# amp_schematic.net
KiCad netlist of a schematic drawn in EAGLE
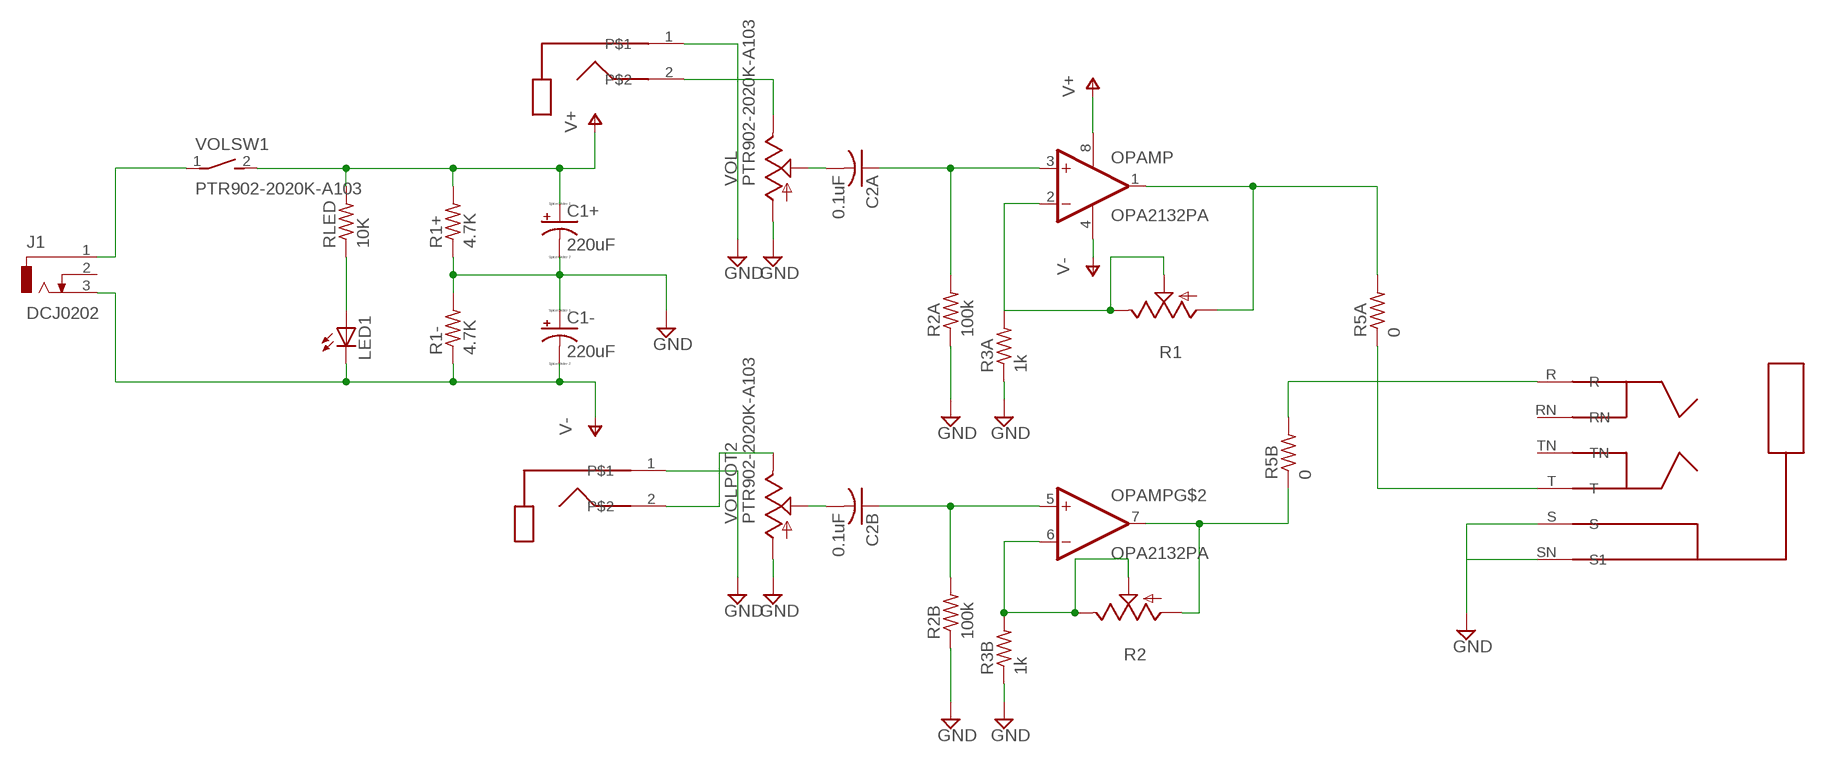
[diagram p0: schematic, sheet 1]

(export (version "E")
  (design (tool "Eeschema 10.0.6"))
  (components
    (comp (ref "C1+")
      (value "220uF")
      (footprint "eagle-import:E3,5-8")
      (libsource (lib "eagle-import") (part "CPOL-USE3.5-8"))
    )
    (comp (ref "C1-")
      (value "220uF")
      (footprint "eagle-import:E3,5-8")
      (libsource (lib "eagle-import") (part "CPOL-USE3.5-8"))
    )
    (comp (ref "C2A")
      (value "0.1uF")
      (footprint "eagle-import:C050-025X075")
      (libsource (lib "eagle-import") (part "C-US050-025X075"))
    )
    (comp (ref "C2B")
      (value "0.1uF")
      (footprint "eagle-import:C050-025X075")
      (libsource (lib "eagle-import") (part "C-US050-025X075"))
    )
    (comp (ref "J1")
      (value "DCJ0202")
      (footprint "eagle-import:DCJ0202")
      (libsource (lib "eagle-import") (part "DCJ0202"))
    )
    (comp (ref "LED1")
      (value "LED5MM")
      (footprint "eagle-import:LED5MM")
      (libsource (lib "eagle-import") (part "LED5MM"))
    )
    (comp (ref "LEFT")
      (value "RCAJACK")
      (footprint "eagle-import:RCAJACK")
      (libsource (lib "eagle-import") (part "RCAJACK"))
    )
    (comp (ref "OPAMP")
      (value "OPA2132PA")
      (footprint "eagle-import:DIP254P762X508-8")
      (fields (field (name "DIGI-KEY_PART_NUMBER") "OPA2132PA-ND") (field (name "MF") "Texas Instruments"))
      (libsource (lib "eagle-import") (part "OPA2132PA"))
    )
    (comp (ref "OUTPUT")
      (value "STEROJACK")
      (footprint "eagle-import:STEREOJACK")
      (libsource (lib "eagle-import") (part "STEROJACK"))
    )
    (comp (ref "R1")
      (value "TRIM_US-B25U")
      (footprint "eagle-import:B25U")
      (libsource (lib "eagle-import") (part "TRIM_US-B25U"))
    )
    (comp (ref "R1+")
      (value "4.7K")
      (footprint "eagle-import:0204V")
      (libsource (lib "eagle-import") (part "R-US_0204/2V"))
    )
    (comp (ref "R1-")
      (value "4.7K")
      (footprint "eagle-import:0204V")
      (libsource (lib "eagle-import") (part "R-US_0204/2V"))
    )
    (comp (ref "R2")
      (value "TRIM_US-B25U")
      (footprint "eagle-import:B25U")
      (libsource (lib "eagle-import") (part "TRIM_US-B25U"))
    )
    (comp (ref "R2A")
      (value "100k")
      (footprint "eagle-import:0204V")
      (libsource (lib "eagle-import") (part "R-US_0204/2V"))
    )
    (comp (ref "R2B")
      (value "100k")
      (footprint "eagle-import:0204V")
      (libsource (lib "eagle-import") (part "R-US_0204/2V"))
    )
    (comp (ref "R3A")
      (value "1k")
      (footprint "eagle-import:0204V")
      (libsource (lib "eagle-import") (part "R-US_0204/2V"))
    )
    (comp (ref "R3B")
      (value "1k")
      (footprint "eagle-import:0204V")
      (libsource (lib "eagle-import") (part "R-US_0204/2V"))
    )
    (comp (ref "R5A")
      (value "0")
      (footprint "eagle-import:0204V")
      (libsource (lib "eagle-import") (part "R-US_0204/2V"))
    )
    (comp (ref "R5B")
      (value "0")
      (footprint "eagle-import:0204V")
      (libsource (lib "eagle-import") (part "R-US_0204/2V"))
    )
    (comp (ref "RIGHT")
      (value "RCAJACK")
      (footprint "eagle-import:RCAJACK")
      (libsource (lib "eagle-import") (part "RCAJACK"))
    )
    (comp (ref "RLED")
      (value "10K")
      (footprint "eagle-import:0204V")
      (libsource (lib "eagle-import") (part "R-US_0204/2V"))
    )
    (comp (ref "VOL")
      (value "PTR902-2020K-A103")
      (footprint "eagle-import:PTR902")
      (libsource (lib "eagle-import") (part "PTR902-2020K-A103"))
    )
  )
  (nets
    (net (code "1") (name "GND") (class "Default")
      (node (ref "C1+") (pin "-") (pinfunction "-_-") (pintype "passive"))
      (node (ref "C1-") (pin "+") (pinfunction "+_+") (pintype "passive"))
      (node (ref "LEFT") (pin "1") (pinfunction "P$1_1") (pintype "bidirectional"))
      (node (ref "OUTPUT") (pin "S") (pinfunction "S_S") (pintype "bidirectional"))
      (node (ref "OUTPUT") (pin "SN") (pinfunction "S1_SN") (pintype "bidirectional"))
      (node (ref "R1+") (pin "1") (pinfunction "1_1") (pintype "passive"))
      (node (ref "R1-") (pin "2") (pinfunction "2_2") (pintype "passive"))
      (node (ref "R2A") (pin "1") (pinfunction "1_1") (pintype "passive"))
      (node (ref "R2B") (pin "1") (pinfunction "1_1") (pintype "passive"))
      (node (ref "R3A") (pin "1") (pinfunction "1_1") (pintype "passive"))
      (node (ref "R3B") (pin "1") (pinfunction "1_1") (pintype "passive"))
      (node (ref "RIGHT") (pin "1") (pinfunction "P$1_1") (pintype "bidirectional"))
      (node (ref "VOL") (pin "1A") (pinfunction "A_1A") (pintype "passive"))
      (node (ref "VOL") (pin "1B") (pinfunction "A_1B") (pintype "passive"))
    )
    (net (code "2") (name "Net-(LED1-PadA)") (class "Default")
      (node (ref "LED1") (pin "A") (pinfunction "A_A") (pintype "passive"))
      (node (ref "RLED") (pin "1") (pinfunction "1_1") (pintype "passive"))
    )
    (net (code "3") (name "Net-(LEFT-P$2)") (class "Default")
      (node (ref "LEFT") (pin "2") (pinfunction "P$2_2") (pintype "bidirectional"))
      (node (ref "VOL") (pin "3A") (pinfunction "E_3A") (pintype "passive"))
    )
    (net (code "4") (name "Net-(OPAMPA-+INA)") (class "Default")
      (node (ref "C2A") (pin "1") (pinfunction "1_1") (pintype "passive"))
      (node (ref "OPAMP") (pin "3") (pinfunction "+INA_3") (pintype "input"))
      (node (ref "R2A") (pin "2") (pinfunction "2_2") (pintype "passive"))
    )
    (net (code "5") (name "Net-(OPAMPA--INA)") (class "Default")
      (node (ref "OPAMP") (pin "2") (pinfunction "-INA_2") (pintype "input"))
      (node (ref "R1") (pin "E") (pinfunction "E_E") (pintype "passive"))
      (node (ref "R1") (pin "S") (pinfunction "S_S") (pintype "passive"))
      (node (ref "R3A") (pin "2") (pinfunction "2_2") (pintype "passive"))
    )
    (net (code "6") (name "Net-(OPAMPA-OUTA)") (class "Default")
      (node (ref "OPAMP") (pin "1") (pinfunction "OUTA_1") (pintype "output"))
      (node (ref "R1") (pin "A") (pinfunction "A_A") (pintype "passive"))
      (node (ref "R5A") (pin "2") (pinfunction "2_2") (pintype "passive"))
    )
    (net (code "7") (name "Net-(OPAMPB-+INB)") (class "Default")
      (node (ref "C2B") (pin "1") (pinfunction "1_1") (pintype "passive"))
      (node (ref "OPAMP") (pin "5") (pinfunction "+INB_5") (pintype "input"))
      (node (ref "R2B") (pin "2") (pinfunction "2_2") (pintype "passive"))
    )
    (net (code "8") (name "Net-(OPAMPB--INB)") (class "Default")
      (node (ref "OPAMP") (pin "6") (pinfunction "-INB_6") (pintype "input"))
      (node (ref "R2") (pin "E") (pinfunction "E_E") (pintype "passive"))
      (node (ref "R2") (pin "S") (pinfunction "S_S") (pintype "passive"))
      (node (ref "R3B") (pin "2") (pinfunction "2_2") (pintype "passive"))
    )
    (net (code "9") (name "Net-(OPAMPB-OUTB)") (class "Default")
      (node (ref "OPAMP") (pin "7") (pinfunction "OUTB_7") (pintype "output"))
      (node (ref "R2") (pin "A") (pinfunction "A_A") (pintype "passive"))
      (node (ref "R5B") (pin "1") (pinfunction "1_1") (pintype "passive"))
    )
    (net (code "10") (name "Net-(OUTPUT-PadR)") (class "Default")
      (node (ref "OUTPUT") (pin "R") (pinfunction "R_R") (pintype "bidirectional"))
      (node (ref "R5B") (pin "2") (pinfunction "2_2") (pintype "passive"))
    )
    (net (code "11") (name "Net-(OUTPUT-PadT)") (class "Default")
      (node (ref "OUTPUT") (pin "T") (pinfunction "T_T") (pintype "bidirectional"))
      (node (ref "R5A") (pin "1") (pinfunction "1_1") (pintype "passive"))
    )
    (net (code "12") (name "Net-(RIGHT-P$2)") (class "Default")
      (node (ref "RIGHT") (pin "2") (pinfunction "P$2_2") (pintype "bidirectional"))
      (node (ref "VOL") (pin "3B") (pinfunction "E_3B") (pintype "passive"))
    )
    (net (code "13") (name "Net-(VOLA-S)") (class "Default")
      (node (ref "C2A") (pin "2") (pinfunction "2_2") (pintype "passive"))
      (node (ref "VOL") (pin "2A") (pinfunction "S_2A") (pintype "passive"))
    )
    (net (code "14") (name "Net-(VOLB-S)") (class "Default")
      (node (ref "C2B") (pin "2") (pinfunction "2_2") (pintype "passive"))
      (node (ref "VOL") (pin "2B") (pinfunction "S_2B") (pintype "passive"))
    )
    (net (code "15") (name "Net-(VOLC-P)") (class "Default")
      (node (ref "J1") (pin "1") (pinfunction "1_1") (pintype "passive"))
      (node (ref "VOL") (pin "1") (pinfunction "P_1") (pintype "passive"))
    )
    (net (code "16") (name "V+") (class "Default")
      (node (ref "C1+") (pin "+") (pinfunction "+_+") (pintype "passive"))
      (node (ref "OPAMP") (pin "8") (pinfunction "V+_8") (pintype "power_in"))
      (node (ref "R1+") (pin "2") (pinfunction "2_2") (pintype "passive"))
      (node (ref "RLED") (pin "2") (pinfunction "2_2") (pintype "passive"))
      (node (ref "VOL") (pin "2") (pinfunction "S_2") (pintype "passive"))
    )
    (net (code "17") (name "V-") (class "Default")
      (node (ref "C1-") (pin "-") (pinfunction "-_-") (pintype "passive"))
      (node (ref "J1") (pin "3") (pinfunction "3_3") (pintype "passive"))
      (node (ref "LED1") (pin "K") (pinfunction "C_K") (pintype "passive"))
      (node (ref "OPAMP") (pin "4") (pinfunction "V-_4") (pintype "power_in"))
      (node (ref "R1-") (pin "1") (pinfunction "1_1") (pintype "passive"))
    )
    (net (code "18") (name "unconnected-(J1-Pad2)") (class "Default")
      (node (ref "J1") (pin "2") (pinfunction "2_2") (pintype "passive"))
    )
    (net (code "19") (name "unconnected-(OUTPUT-PadRN)") (class "Default")
      (node (ref "OUTPUT") (pin "RN") (pinfunction "RN_RN") (pintype "bidirectional"))
    )
    (net (code "20") (name "unconnected-(OUTPUT-PadTN)") (class "Default")
      (node (ref "OUTPUT") (pin "TN") (pinfunction "TN_TN") (pintype "bidirectional"))
    )
  )
)
